# HG0B1CEU.net
KiCad netlist of a schematic drawn in EAGLE
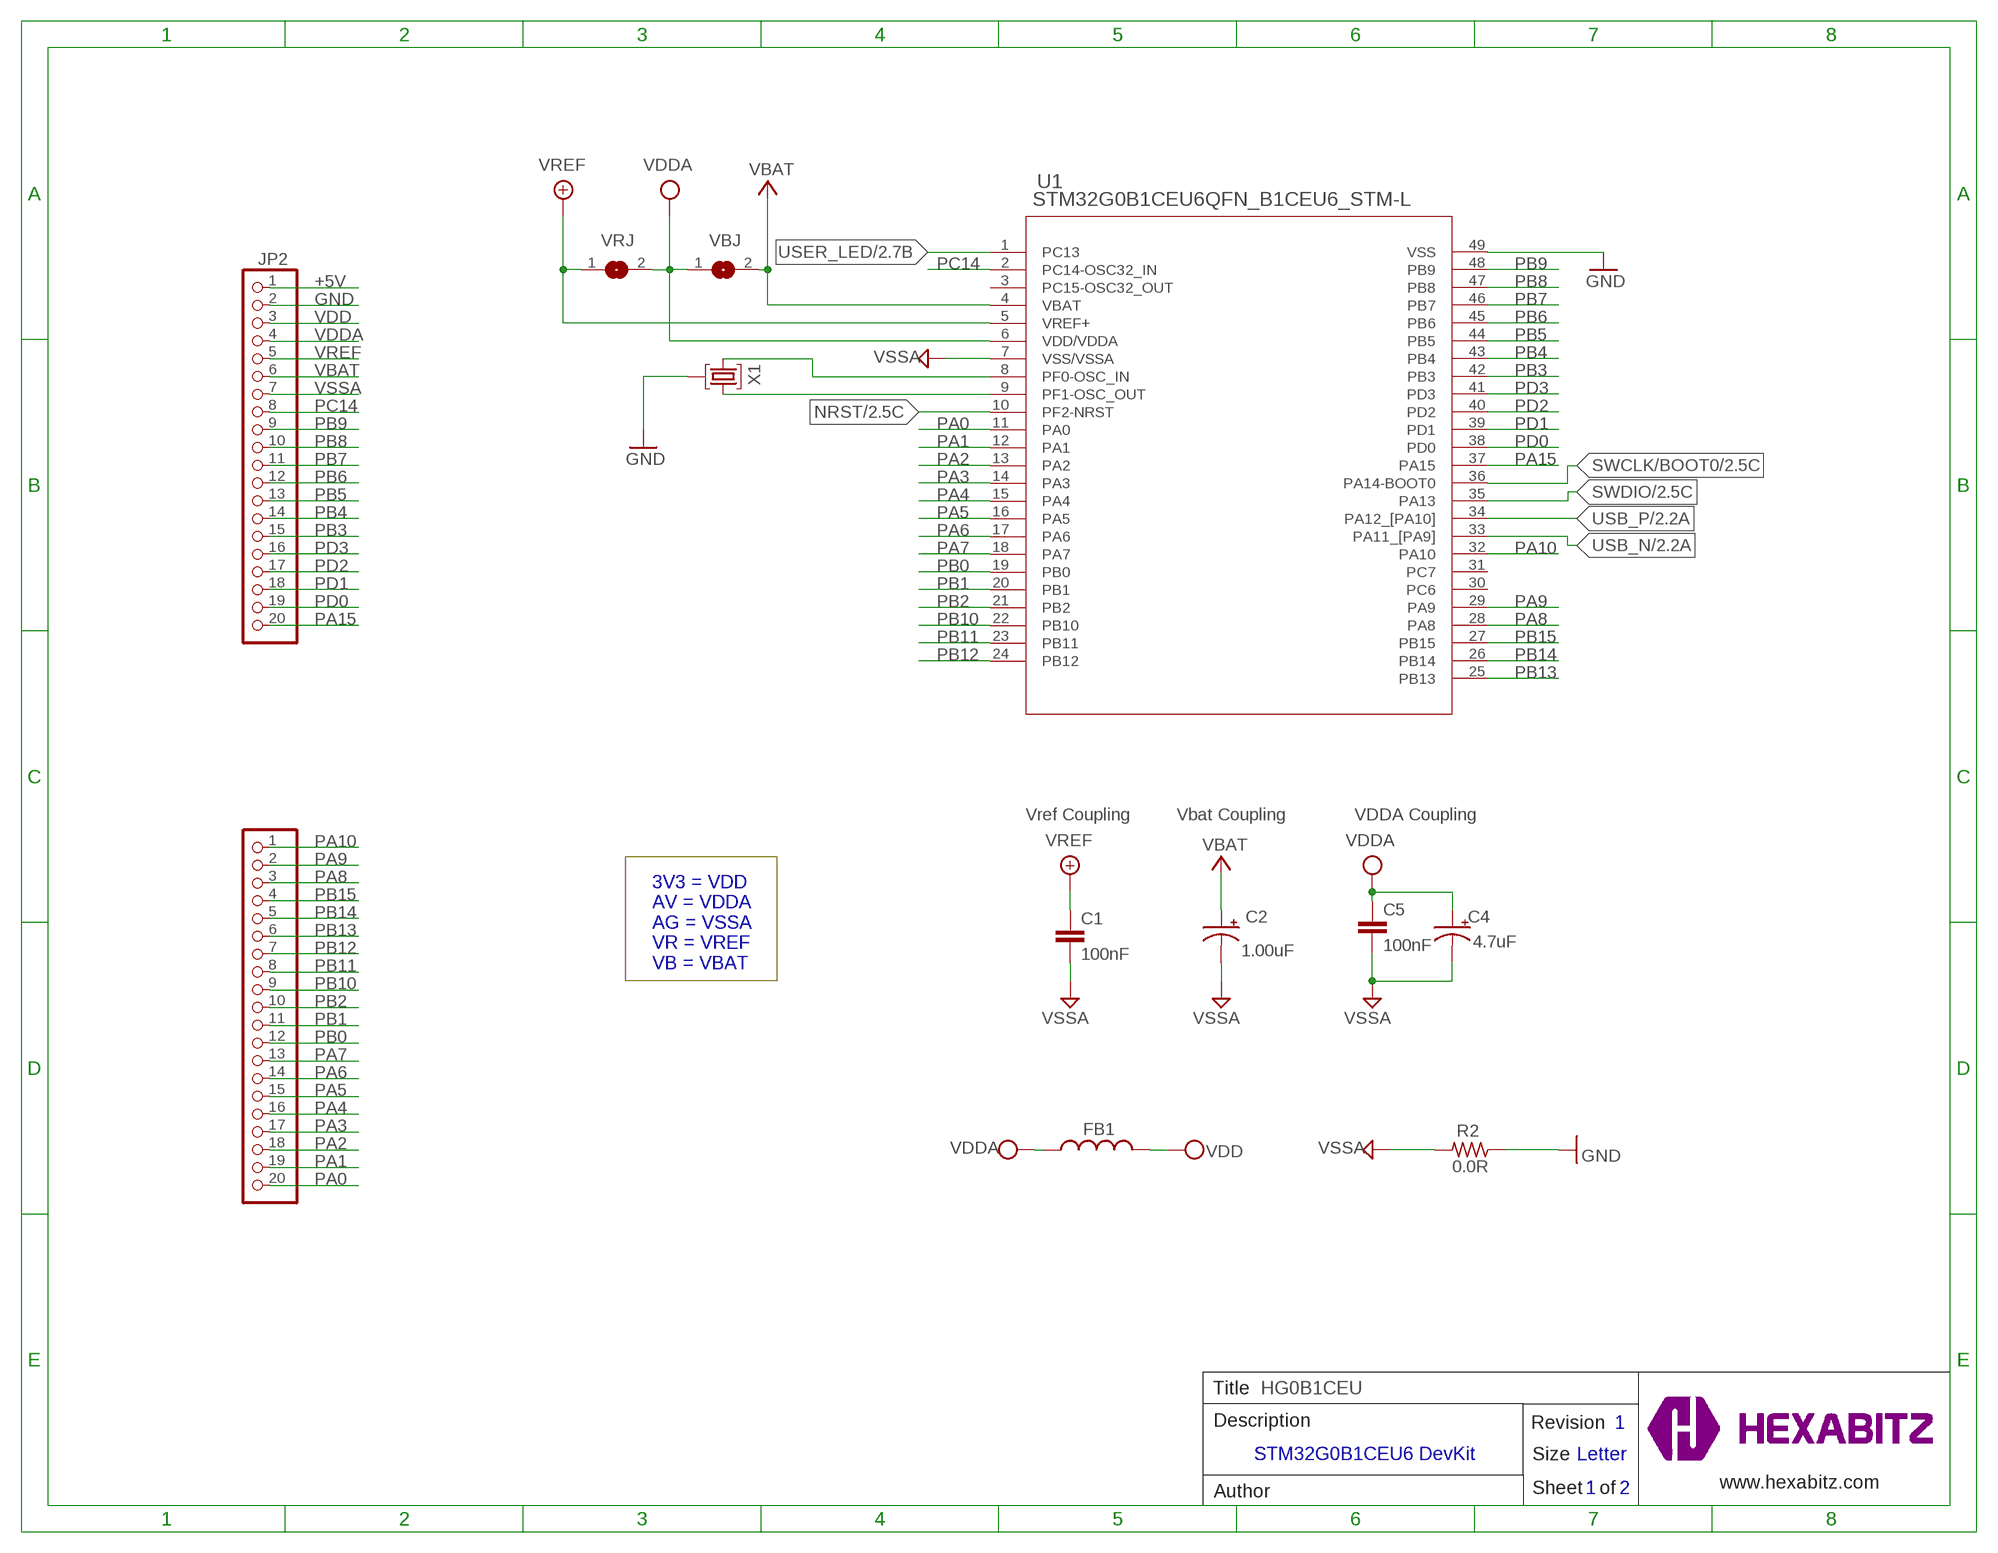
[diagram p0: schematic, sheet 1]
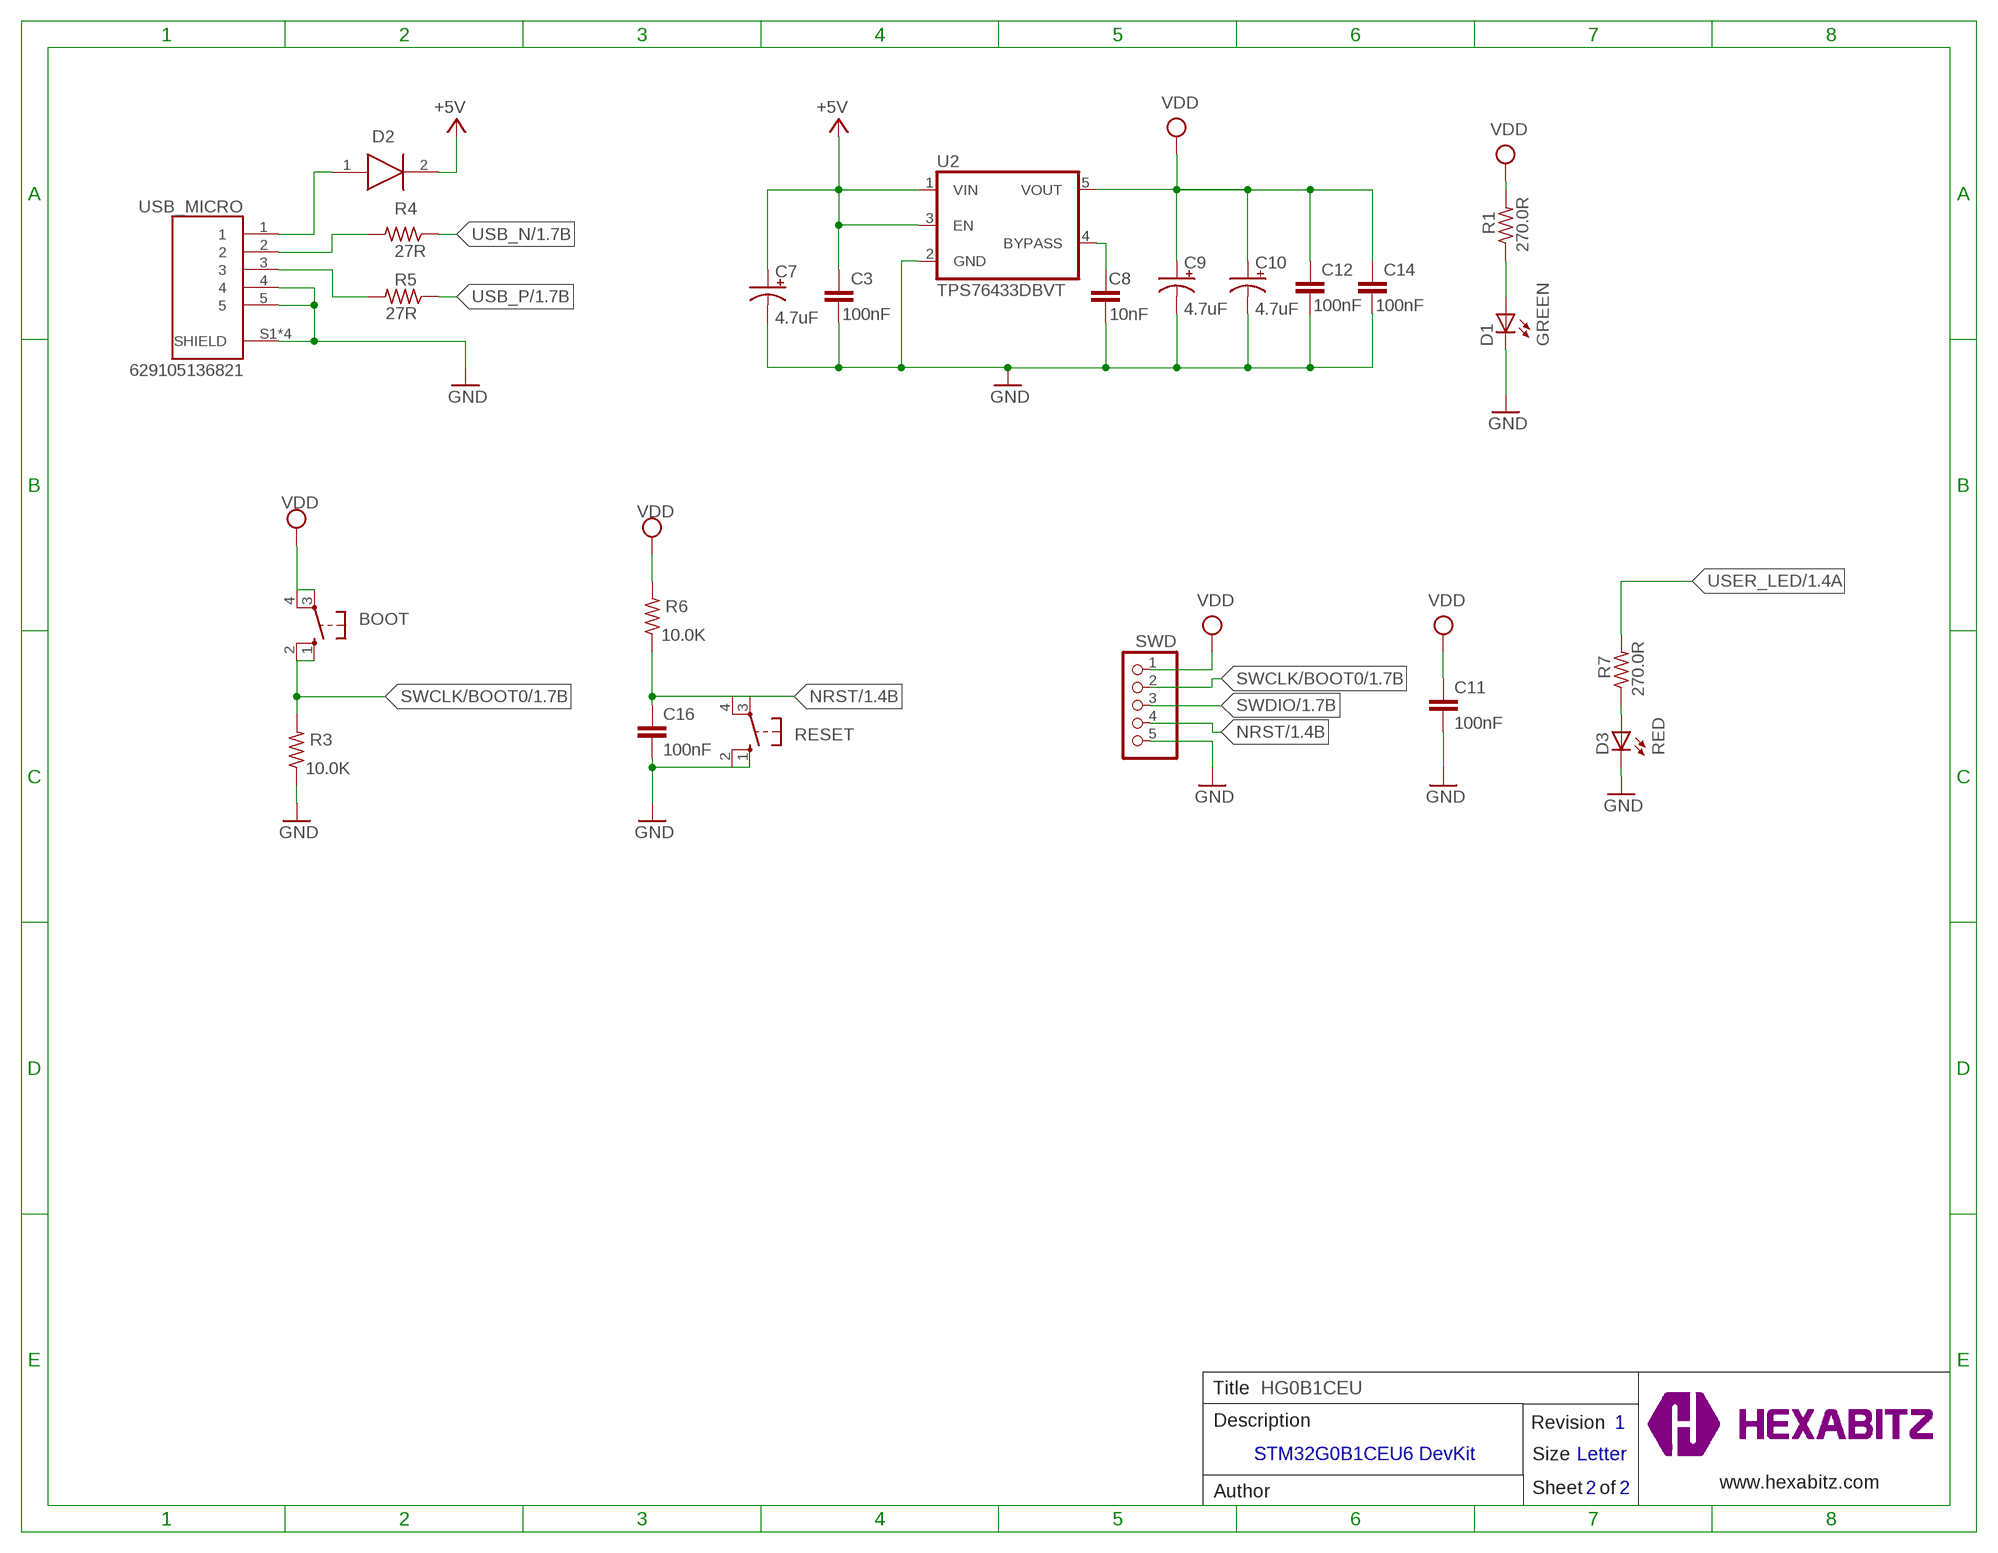
[diagram p1: schematic, sheet 2]

(export (version "E")
  (design (tool "Eeschema 10.0.6"))
  (components
    (comp (ref "BOOT")
      (value "10-XX")
      (footprint "eagle-import:B3F-10XX")
      (fields (field (name "MPN") "B3F-1000"))
      (libsource (lib "eagle-import") (part "10-XX"))
    )
    (comp (ref "C3")
      (value "100nF")
      (footprint "eagle-import:C-0603")
      (fields
        (field (name "CAPACITANCE") "100nF")
        (field (name "MFN") "KEMET")
        (field (name "MPN") "C0603C104K8RACTU")
        (field (name "OCTOPART_URL") "https://octopart.com/c0603c104k8ractu-kemet-145075?r=sp&s=9bS9ASSwSEqMCE9KBEQZ0g")
        (field (name "TOLERANCE") "10%")
        (field (name "VOLTAGE_RATING") "10")
      )
      (libsource (lib "eagle-import") (part "C-0603"))
    )
    (comp (ref "C7")
      (value "4.7uF")
      (footprint "eagle-import:C-0805-POL")
      (fields
        (field (name "CAPACITANCE") "4.7uF")
        (field (name "MFN") "Murata")
        (field (name "MPN") "GRM21BC81E475KA12L")
        (field (name "OCTOPART_URL") "https://octopart.com/grm21bc81e475ka12l-murata-10331911?r=sp&s=RY3qZSD8T6mG6TC9CHI5qQ")
        (field (name "TOLERANCE") "10%")
        (field (name "VOLTAGE_RATING") "25V")
      )
      (libsource (lib "eagle-import") (part "C-0805-POL"))
    )
    (comp (ref "C8")
      (value "10nF")
      (footprint "eagle-import:C-0603")
      (fields
        (field (name "CAPACITANCE") "100nF")
        (field (name "MFN") "KEMET")
        (field (name "MPN") "C0603C104K8RACTU")
        (field (name "OCTOPART_URL") "https://octopart.com/c0603c104k8ractu-kemet-145075?r=sp&s=9bS9ASSwSEqMCE9KBEQZ0g")
        (field (name "TOLERANCE") "10%")
        (field (name "VOLTAGE_RATING") "10")
      )
      (libsource (lib "eagle-import") (part "C-0603"))
    )
    (comp (ref "C9")
      (value "4.7uF")
      (footprint "eagle-import:C-0805-POL")
      (fields
        (field (name "CAPACITANCE") "4.7uF")
        (field (name "MFN") "Murata")
        (field (name "MPN") "GRM21BC81E475KA12L")
        (field (name "OCTOPART_URL") "https://octopart.com/grm21bc81e475ka12l-murata-10331911?r=sp&s=RY3qZSD8T6mG6TC9CHI5qQ")
        (field (name "TOLERANCE") "10%")
        (field (name "VOLTAGE_RATING") "25V")
      )
      (libsource (lib "eagle-import") (part "C-0805-POL"))
    )
    (comp (ref "C10")
      (value "4.7uF")
      (footprint "eagle-import:C-0805-POL")
      (fields
        (field (name "CAPACITANCE") "4.7uF")
        (field (name "MFN") "Murata")
        (field (name "MPN") "GRM21BC81E475KA12L")
        (field (name "OCTOPART_URL") "https://octopart.com/grm21bc81e475ka12l-murata-10331911?r=sp&s=RY3qZSD8T6mG6TC9CHI5qQ")
        (field (name "TOLERANCE") "10%")
        (field (name "VOLTAGE_RATING") "25V")
      )
      (libsource (lib "eagle-import") (part "C-0805-POL"))
    )
    (comp (ref "C11")
      (value "100nF")
      (footprint "eagle-import:C-0603")
      (fields
        (field (name "CAPACITANCE") "100nF")
        (field (name "MFN") "KEMET")
        (field (name "MPN") "C0603C104K8RACTU")
        (field (name "OCTOPART_URL") "https://octopart.com/c0603c104k8ractu-kemet-145075?r=sp&s=9bS9ASSwSEqMCE9KBEQZ0g")
        (field (name "TOLERANCE") "10%")
        (field (name "VOLTAGE_RATING") "10V")
      )
      (libsource (lib "eagle-import") (part "C-0603"))
    )
    (comp (ref "C12")
      (value "100nF")
      (footprint "eagle-import:C-0603")
      (fields
        (field (name "CAPACITANCE") "100nF")
        (field (name "MFN") "KEMET")
        (field (name "MPN") "C0603C104K8RACTU")
        (field (name "OCTOPART_URL") "https://octopart.com/c0603c104k8ractu-kemet-145075?r=sp&s=9bS9ASSwSEqMCE9KBEQZ0g")
        (field (name "TOLERANCE") "10%")
        (field (name "VOLTAGE_RATING") "10")
      )
      (libsource (lib "eagle-import") (part "C-0603"))
    )
    (comp (ref "C14")
      (value "100nF")
      (footprint "eagle-import:C-0603")
      (fields
        (field (name "CAPACITANCE") "100nF")
        (field (name "MFN") "KEMET")
        (field (name "MPN") "C0603C104K8RACTU")
        (field (name "OCTOPART_URL") "https://octopart.com/c0603c104k8ractu-kemet-145075?r=sp&s=9bS9ASSwSEqMCE9KBEQZ0g")
        (field (name "TOLERANCE") "10%")
        (field (name "VOLTAGE_RATING") "10")
      )
      (libsource (lib "eagle-import") (part "C-0603"))
    )
    (comp (ref "C16")
      (value "100nF")
      (footprint "eagle-import:C-0603")
      (fields
        (field (name "CAPACITANCE") "100nF")
        (field (name "MFN") "KEMET")
        (field (name "MPN") "C0603C104K8RACTU")
        (field (name "OCTOPART_URL") "https://octopart.com/c0603c104k8ractu-kemet-145075?r=sp&s=9bS9ASSwSEqMCE9KBEQZ0g")
        (field (name "TOLERANCE") "10%")
        (field (name "VOLTAGE_RATING") "10V")
      )
      (libsource (lib "eagle-import") (part "C-0603"))
    )
    (comp (ref "D1")
      (value "GREEN")
      (footprint "eagle-import:VLMS1300-GS08")
      (fields
        (field (name "MPN") "VLMS1300-GS08")
        (field (name "MFN") "Vishay")
        (field (name "MPN_1") "VLMS1300-GS08")
        (field (name "OCTOPART_URL") "https://octopart.com/vlms1300-gs08-vishay-21709201?r=sp&s=_gcP4_q8T1SC6PJQPTQ9yA")
      )
      (libsource (lib "eagle-import") (part "VLMS1300-GS08"))
    )
    (comp (ref "D2")
      (value "FSM17PL-TP")
      (footprint "eagle-import:FSM17PL-TP")
      (libsource (lib "eagle-import") (part "FSM17PL-TP"))
    )
    (comp (ref "D3")
      (value "RED")
      (footprint "eagle-import:VLMS1300-GS08")
      (fields
        (field (name "MPN") "VLMS1300-GS08")
        (field (name "MFN") "Vishay")
        (field (name "MPN_1") "VLMS1300-GS08")
        (field (name "OCTOPART_URL") "https://octopart.com/vlms1300-gs08-vishay-21709201?r=sp&s=_gcP4_q8T1SC6PJQPTQ9yA")
      )
      (libsource (lib "eagle-import") (part "VLMS1300-GS08"))
    )
    (comp (ref "R1")
      (value "270.0R")
      (footprint "eagle-import:R-0603")
      (fields
        (field (name "MFN") "Yageo")
        (field (name "MPN") "RC0603FR-07270RL")
        (field (name "OCTOPART_URL") "https://octopart.com/search?q=RC0603FR-07270RL&start=0")
        (field (name "RESISTANCE") "270.0 Ohm")
        (field (name "TOLERANCE") "1%")
      )
      (libsource (lib "eagle-import") (part "R-0603"))
    )
    (comp (ref "R3")
      (value "10.0K")
      (footprint "eagle-import:R-0603")
      (fields
        (field (name "MFN") "Yageo")
        (field (name "MPN") "RC0603JR-0710KL")
        (field (name "OCTOPART_URL") "https://octopart.com/search?q=RC0603JR-0710KL&start=0")
        (field (name "RESISTANCE") "10.0K Ohm")
        (field (name "TOLERANCE") "5%")
      )
      (libsource (lib "eagle-import") (part "R-0603"))
    )
    (comp (ref "R4")
      (value "27R")
      (footprint "eagle-import:R-0603")
      (fields
        (field (name "MFN") "Yageo")
        (field (name "MPN") "RC0603JR-0710KL")
        (field (name "OCTOPART_URL") "https://octopart.com/search?q=RC0603JR-0710KL&start=0")
        (field (name "RESISTANCE") "10.0K Ohm")
        (field (name "TOLERANCE") "5%")
      )
      (libsource (lib "eagle-import") (part "R-0603"))
    )
    (comp (ref "R5")
      (value "27R")
      (footprint "eagle-import:R-0603")
      (fields
        (field (name "MFN") "Yageo")
        (field (name "MPN") "RC0603JR-0710KL")
        (field (name "OCTOPART_URL") "https://octopart.com/search?q=RC0603JR-0710KL&start=0")
        (field (name "RESISTANCE") "10.0K Ohm")
        (field (name "TOLERANCE") "5%")
      )
      (libsource (lib "eagle-import") (part "R-0603"))
    )
    (comp (ref "R6")
      (value "10.0K")
      (footprint "eagle-import:R-0603")
      (fields
        (field (name "MFN") "Yageo")
        (field (name "MPN") "RC0603JR-0710KL")
        (field (name "OCTOPART_URL") "https://octopart.com/search?q=RC0603JR-0710KL&start=0")
        (field (name "RESISTANCE") "10.0K Ohm")
        (field (name "TOLERANCE") "5%")
      )
      (libsource (lib "eagle-import") (part "R-0603"))
    )
    (comp (ref "R7")
      (value "270.0R")
      (footprint "eagle-import:R-0603")
      (fields
        (field (name "MFN") "Yageo")
        (field (name "MPN") "RC0603FR-07270RL")
        (field (name "OCTOPART_URL") "https://octopart.com/search?q=RC0603FR-07270RL&start=0")
        (field (name "RESISTANCE") "270.0 Ohm")
        (field (name "TOLERANCE") "1%")
      )
      (libsource (lib "eagle-import") (part "R-0603"))
    )
    (comp (ref "RESET")
      (value "10-XX")
      (footprint "eagle-import:B3F-10XX")
      (fields (field (name "MPN") "B3F-1000"))
      (libsource (lib "eagle-import") (part "10-XX"))
    )
    (comp (ref "SWD")
      (value "PINHD-1X5/90")
      (footprint "eagle-import:1X05_90")
      (libsource (lib "eagle-import") (part "PINHD-1X5/90"))
    )
    (comp (ref "U2")
      (value "TPS76433DBVT")
      (footprint "eagle-import:SOT25")
      (libsource (lib "eagle-import") (part "TPS764DBVT33"))
    )
    (comp (ref "USB_MICRO")
      (value "629105136821")
      (footprint "eagle-import:WE_629105136821")
      (fields (field (name "MF") "Würth Elektronik"))
      (libsource (lib "eagle-import") (part "629105136821"))
    )
    (comp (ref "C1")
      (value "100nF")
      (footprint "eagle-import:C-0603")
      (fields
        (field (name "CAPACITANCE") "100nF")
        (field (name "MFN") "KEMET")
        (field (name "MPN") "C0603C104K8RACTU")
        (field (name "OCTOPART_URL") "https://octopart.com/c0603c104k8ractu-kemet-145075?r=sp&s=9bS9ASSwSEqMCE9KBEQZ0g")
        (field (name "TOLERANCE") "10%")
        (field (name "VOLTAGE_RATING") "10V")
      )
      (libsource (lib "eagle-import") (part "C-0603"))
    )
    (comp (ref "C2")
      (value "1.00uF")
      (footprint "eagle-import:C-0805-POL")
      (fields
        (field (name "CAPACITANCE") "1.00uF")
        (field (name "MFN") "Yageo")
        (field (name "MPN") "CC0805KKX7R7BB105")
        (field (name "OCTOPART_URL") "https://octopart.com/cc0805kkx7r7bb105-yageo-8376555?r=sp&s=YKl1wwtkROau_X5nniH2ig")
        (field (name "TOLERANCE") "10%")
        (field (name "VOLTAGE_RATING") "16V")
      )
      (libsource (lib "eagle-import") (part "C-0805-POL"))
    )
    (comp (ref "C4")
      (value "4.7uF")
      (footprint "eagle-import:C-0805-POL")
      (fields
        (field (name "CAPACITANCE") "4.7uF")
        (field (name "MFN") "Murata")
        (field (name "MPN") "GRM21BC81E475KA12L")
        (field (name "OCTOPART_URL") "https://octopart.com/grm21bc81e475ka12l-murata-10331911?r=sp&s=RY3qZSD8T6mG6TC9CHI5qQ")
        (field (name "TOLERANCE") "10%")
        (field (name "VOLTAGE_RATING") "25V")
      )
      (libsource (lib "eagle-import") (part "C-0805-POL"))
    )
    (comp (ref "C5")
      (value "100nF")
      (footprint "eagle-import:C-0603")
      (fields
        (field (name "CAPACITANCE") "100nF")
        (field (name "MFN") "KEMET")
        (field (name "MPN") "C0603C104K8RACTU")
        (field (name "OCTOPART_URL") "https://octopart.com/c0603c104k8ractu-kemet-145075?r=sp&s=9bS9ASSwSEqMCE9KBEQZ0g")
        (field (name "TOLERANCE") "10%")
        (field (name "VOLTAGE_RATING") "10")
      )
      (libsource (lib "eagle-import") (part "C-0603"))
    )
    (comp (ref "FB1")
      (value "FB-TDK_MMZ1608Y300B")
      (footprint "eagle-import:FB-TDK_MMZ1608Y300B")
      (fields
        (field (name "MFN") "TDK ")
        (field (name "MPN") "MMZ1608Y300B")
        (field (name "OCTOPART_URL") "https://octopart.com/mmz1608y300b-tdk-368280?r=sp&s=cd9_2ZEqQ9q9UNBuQgHAiA")
      )
      (libsource (lib "eagle-import") (part "FB-TDK_MMZ1608Y300B"))
    )
    (comp (ref "JP1")
      (value "PINHD-1X20")
      (footprint "eagle-import:1X20")
      (libsource (lib "eagle-import") (part "PINHD-1X20"))
    )
    (comp (ref "JP2")
      (value "PINHD-1X20")
      (footprint "eagle-import:1X20")
      (libsource (lib "eagle-import") (part "PINHD-1X20"))
    )
    (comp (ref "R2")
      (value "0.0R")
      (footprint "eagle-import:R-0603")
      (fields
        (field (name "MFN") "Yageo")
        (field (name "MPN") "RC0603JR-070RL")
        (field (name "OCTOPART_URL") "https://octopart.com/rc0603jr-070rl-yageo-1241539?r=sp&s=X2NteqRjRNWrnx42Y0aliA")
        (field (name "RESISTANCE") "0.0 Ohm")
      )
      (libsource (lib "eagle-import") (part "R-0603"))
    )
    (comp (ref "U1")
      (value "STM32G0B1CEU6QFN_B1CEU6_STM-L")
      (footprint "eagle-import:QFN_B1CEU6_STM-L")
      (fields
        (field (name "MANUFACTURER_PART_NUMBER") "STM32G0B1CEU6")
        (field (name "COPYRIGHT") "Copyright (C) 2021 Ultra Librarian. All rights reserved.")
      )
      (libsource (lib "eagle-import") (part "STM32G0B1CEU6QFN_B1CEU6_STM-L"))
    )
    (comp (ref "VBJ") (value "SJ") (footprint "eagle-import:SJ") (libsource (lib "eagle-import") (part "SJ")))
    (comp (ref "VRJ") (value "SJ") (footprint "eagle-import:SJ") (libsource (lib "eagle-import") (part "SJ")))
    (comp (ref "X1")
      (value "XTALL_CSTCE8M00G52")
      (footprint "eagle-import:XTALL_CSTCE8M00G52")
      (fields (field (name "MPN") "CSTCE8M00G52Z-R0"))
      (libsource (lib "eagle-import") (part "XTALL_CSTCE8M00G52"))
    )
  )
  (nets
    (net (code "1") (name "+5V") (class "Default")
      (node (ref "C3") (pin "1") (pinfunction "1_1") (pintype "passive"))
      (node (ref "C7") (pin "1") (pinfunction "+_1") (pintype "passive"))
      (node (ref "D2") (pin "2") (pinfunction "K_2") (pintype "bidirectional"))
      (node (ref "JP2") (pin "1") (pinfunction "1_1") (pintype "passive"))
      (node (ref "U2") (pin "1") (pinfunction "VIN_1") (pintype "input"))
      (node (ref "U2") (pin "3") (pinfunction "EN_3") (pintype "input"))
    )
    (net (code "2") (name "GND") (class "Default")
      (node (ref "C10") (pin "2") (pinfunction "-_2") (pintype "passive"))
      (node (ref "C11") (pin "2") (pinfunction "2_2") (pintype "passive"))
      (node (ref "C12") (pin "2") (pinfunction "2_2") (pintype "passive"))
      (node (ref "C14") (pin "2") (pinfunction "2_2") (pintype "passive"))
      (node (ref "C16") (pin "2") (pinfunction "2_2") (pintype "passive"))
      (node (ref "C3") (pin "2") (pinfunction "2_2") (pintype "passive"))
      (node (ref "C7") (pin "2") (pinfunction "-_2") (pintype "passive"))
      (node (ref "C8") (pin "2") (pinfunction "2_2") (pintype "passive"))
      (node (ref "C9") (pin "2") (pinfunction "-_2") (pintype "passive"))
      (node (ref "D1") (pin "C") (pinfunction "C_C") (pintype "passive"))
      (node (ref "D3") (pin "C") (pinfunction "C_C") (pintype "passive"))
      (node (ref "JP2") (pin "2") (pinfunction "2_2") (pintype "passive"))
      (node (ref "R2") (pin "1") (pinfunction "1_1") (pintype "passive"))
      (node (ref "R3") (pin "1") (pinfunction "1_1") (pintype "passive"))
      (node (ref "RESET") (pin "1") (pinfunction "S_1") (pintype "passive"))
      (node (ref "RESET") (pin "2") (pinfunction "S1_2") (pintype "passive"))
      (node (ref "SWD") (pin "5") (pinfunction "5_5") (pintype "passive"))
      (node (ref "U1") (pin "49") (pinfunction "VSS_49") (pintype "passive"))
      (node (ref "U2") (pin "2") (pinfunction "GND_2") (pintype "passive"))
      (node (ref "USB_MICRO") (pin "4") (pinfunction "4_4") (pintype "passive"))
      (node (ref "USB_MICRO") (pin "5") (pinfunction "5_5") (pintype "passive"))
      (node (ref "USB_MICRO") (pin "S1") (pinfunction "SHIELD_S1") (pintype "passive"))
      (node (ref "USB_MICRO") (pin "S2") (pinfunction "SHIELD_S2") (pintype "passive"))
      (node (ref "USB_MICRO") (pin "S3") (pinfunction "SHIELD_S3") (pintype "passive"))
      (node (ref "USB_MICRO") (pin "S4") (pinfunction "SHIELD_S4") (pintype "passive"))
      (node (ref "X1") (pin "P$2") (pinfunction "2_P$2") (pintype "passive"))
    )
    (net (code "3") (name "NRST") (class "Default")
      (node (ref "C16") (pin "1") (pinfunction "1_1") (pintype "passive"))
      (node (ref "R6") (pin "1") (pinfunction "1_1") (pintype "passive"))
      (node (ref "RESET") (pin "3") (pinfunction "P_3") (pintype "passive"))
      (node (ref "RESET") (pin "4") (pinfunction "P1_4") (pintype "passive"))
      (node (ref "SWD") (pin "4") (pinfunction "4_4") (pintype "passive"))
      (node (ref "U1") (pin "10") (pinfunction "PF2-NRST_10") (pintype "bidirectional"))
    )
    (net (code "4") (name "Net-(D1-PadA)") (class "Default")
      (node (ref "D1") (pin "A") (pinfunction "A_A") (pintype "passive"))
      (node (ref "R1") (pin "1") (pinfunction "1_1") (pintype "passive"))
    )
    (net (code "5") (name "Net-(D2-A)") (class "Default")
      (node (ref "D2") (pin "1") (pinfunction "A_1") (pintype "bidirectional"))
      (node (ref "USB_MICRO") (pin "1") (pinfunction "1_1") (pintype "passive"))
    )
    (net (code "6") (name "Net-(D3-PadA)") (class "Default")
      (node (ref "D3") (pin "A") (pinfunction "A_A") (pintype "passive"))
      (node (ref "R7") (pin "1") (pinfunction "1_1") (pintype "passive"))
    )
    (net (code "7") (name "Net-(R4-Pad2)") (class "Default")
      (node (ref "R4") (pin "2") (pinfunction "2_2") (pintype "passive"))
      (node (ref "USB_MICRO") (pin "2") (pinfunction "2_2") (pintype "passive"))
    )
    (net (code "8") (name "Net-(R5-Pad2)") (class "Default")
      (node (ref "R5") (pin "2") (pinfunction "2_2") (pintype "passive"))
      (node (ref "USB_MICRO") (pin "3") (pinfunction "3_3") (pintype "passive"))
    )
    (net (code "9") (name "Net-(U1-PF0-OSC_IN)") (class "Default")
      (node (ref "U1") (pin "8") (pinfunction "PF0-OSC_IN_8") (pintype "bidirectional"))
      (node (ref "X1") (pin "P$1") (pinfunction "1_P$1") (pintype "passive"))
    )
    (net (code "10") (name "Net-(U1-PF1-OSC_OUT)") (class "Default")
      (node (ref "U1") (pin "9") (pinfunction "PF1-OSC_OUT_9") (pintype "output"))
      (node (ref "X1") (pin "P$3") (pinfunction "3_P$3") (pintype "passive"))
    )
    (net (code "11") (name "Net-(U2-BYPASS)") (class "Default")
      (node (ref "C8") (pin "1") (pinfunction "1_1") (pintype "passive"))
      (node (ref "U2") (pin "4") (pinfunction "BYPASS_4") (pintype "input"))
    )
    (net (code "12") (name "PA0") (class "Default")
      (node (ref "JP1") (pin "20") (pinfunction "20_20") (pintype "passive"))
      (node (ref "U1") (pin "11") (pinfunction "PA0_11") (pintype "bidirectional"))
    )
    (net (code "13") (name "PA1") (class "Default")
      (node (ref "JP1") (pin "19") (pinfunction "19_19") (pintype "passive"))
      (node (ref "U1") (pin "12") (pinfunction "PA1_12") (pintype "bidirectional"))
    )
    (net (code "14") (name "PA2") (class "Default")
      (node (ref "JP1") (pin "18") (pinfunction "18_18") (pintype "passive"))
      (node (ref "U1") (pin "13") (pinfunction "PA2_13") (pintype "bidirectional"))
    )
    (net (code "15") (name "PA3") (class "Default")
      (node (ref "JP1") (pin "17") (pinfunction "17_17") (pintype "passive"))
      (node (ref "U1") (pin "14") (pinfunction "PA3_14") (pintype "bidirectional"))
    )
    (net (code "16") (name "PA4") (class "Default")
      (node (ref "JP1") (pin "16") (pinfunction "16_16") (pintype "passive"))
      (node (ref "U1") (pin "15") (pinfunction "PA4_15") (pintype "bidirectional"))
    )
    (net (code "17") (name "PA5") (class "Default")
      (node (ref "JP1") (pin "15") (pinfunction "15_15") (pintype "passive"))
      (node (ref "U1") (pin "16") (pinfunction "PA5_16") (pintype "bidirectional"))
    )
    (net (code "18") (name "PA6") (class "Default")
      (node (ref "JP1") (pin "14") (pinfunction "14_14") (pintype "passive"))
      (node (ref "U1") (pin "17") (pinfunction "PA6_17") (pintype "bidirectional"))
    )
    (net (code "19") (name "PA7") (class "Default")
      (node (ref "JP1") (pin "13") (pinfunction "13_13") (pintype "passive"))
      (node (ref "U1") (pin "18") (pinfunction "PA7_18") (pintype "bidirectional"))
    )
    (net (code "20") (name "PA8") (class "Default")
      (node (ref "JP1") (pin "3") (pinfunction "3_3") (pintype "passive"))
      (node (ref "U1") (pin "28") (pinfunction "PA8_28") (pintype "bidirectional"))
    )
    (net (code "21") (name "PA9") (class "Default")
      (node (ref "JP1") (pin "2") (pinfunction "2_2") (pintype "passive"))
      (node (ref "U1") (pin "29") (pinfunction "PA9_29") (pintype "bidirectional"))
    )
    (net (code "22") (name "PA10") (class "Default")
      (node (ref "JP1") (pin "1") (pinfunction "1_1") (pintype "passive"))
      (node (ref "U1") (pin "32") (pinfunction "PA10_32") (pintype "bidirectional"))
    )
    (net (code "23") (name "PA15") (class "Default")
      (node (ref "JP2") (pin "20") (pinfunction "20_20") (pintype "passive"))
      (node (ref "U1") (pin "37") (pinfunction "PA15_37") (pintype "bidirectional"))
    )
    (net (code "24") (name "PB0") (class "Default")
      (node (ref "JP1") (pin "12") (pinfunction "12_12") (pintype "passive"))
      (node (ref "U1") (pin "19") (pinfunction "PB0_19") (pintype "bidirectional"))
    )
    (net (code "25") (name "PB1") (class "Default")
      (node (ref "JP1") (pin "11") (pinfunction "11_11") (pintype "passive"))
      (node (ref "U1") (pin "20") (pinfunction "PB1_20") (pintype "bidirectional"))
    )
    (net (code "26") (name "PB2") (class "Default")
      (node (ref "JP1") (pin "10") (pinfunction "10_10") (pintype "passive"))
      (node (ref "U1") (pin "21") (pinfunction "PB2_21") (pintype "bidirectional"))
    )
    (net (code "27") (name "PB3") (class "Default")
      (node (ref "JP2") (pin "15") (pinfunction "15_15") (pintype "passive"))
      (node (ref "U1") (pin "42") (pinfunction "PB3_42") (pintype "bidirectional"))
    )
    (net (code "28") (name "PB4") (class "Default")
      (node (ref "JP2") (pin "14") (pinfunction "14_14") (pintype "passive"))
      (node (ref "U1") (pin "43") (pinfunction "PB4_43") (pintype "bidirectional"))
    )
    (net (code "29") (name "PB5") (class "Default")
      (node (ref "JP2") (pin "13") (pinfunction "13_13") (pintype "passive"))
      (node (ref "U1") (pin "44") (pinfunction "PB5_44") (pintype "bidirectional"))
    )
    (net (code "30") (name "PB6") (class "Default")
      (node (ref "JP2") (pin "12") (pinfunction "12_12") (pintype "passive"))
      (node (ref "U1") (pin "45") (pinfunction "PB6_45") (pintype "bidirectional"))
    )
    (net (code "31") (name "PB7") (class "Default")
      (node (ref "JP2") (pin "11") (pinfunction "11_11") (pintype "passive"))
      (node (ref "U1") (pin "46") (pinfunction "PB7_46") (pintype "bidirectional"))
    )
    (net (code "32") (name "PB8") (class "Default")
      (node (ref "JP2") (pin "10") (pinfunction "10_10") (pintype "passive"))
      (node (ref "U1") (pin "47") (pinfunction "PB8_47") (pintype "bidirectional"))
    )
    (net (code "33") (name "PB9") (class "Default")
      (node (ref "JP2") (pin "9") (pinfunction "9_9") (pintype "passive"))
      (node (ref "U1") (pin "48") (pinfunction "PB9_48") (pintype "bidirectional"))
    )
    (net (code "34") (name "PB10") (class "Default")
      (node (ref "JP1") (pin "9") (pinfunction "9_9") (pintype "passive"))
      (node (ref "U1") (pin "22") (pinfunction "PB10_22") (pintype "bidirectional"))
    )
    (net (code "35") (name "PB11") (class "Default")
      (node (ref "JP1") (pin "8") (pinfunction "8_8") (pintype "passive"))
      (node (ref "U1") (pin "23") (pinfunction "PB11_23") (pintype "bidirectional"))
    )
    (net (code "36") (name "PB12") (class "Default")
      (node (ref "JP1") (pin "7") (pinfunction "7_7") (pintype "passive"))
      (node (ref "U1") (pin "24") (pinfunction "PB12_24") (pintype "bidirectional"))
    )
    (net (code "37") (name "PB13") (class "Default")
      (node (ref "JP1") (pin "6") (pinfunction "6_6") (pintype "passive"))
      (node (ref "U1") (pin "25") (pinfunction "PB13_25") (pintype "bidirectional"))
    )
    (net (code "38") (name "PB14") (class "Default")
      (node (ref "JP1") (pin "5") (pinfunction "5_5") (pintype "passive"))
      (node (ref "U1") (pin "26") (pinfunction "PB14_26") (pintype "bidirectional"))
    )
    (net (code "39") (name "PB15") (class "Default")
      (node (ref "JP1") (pin "4") (pinfunction "4_4") (pintype "passive"))
      (node (ref "U1") (pin "27") (pinfunction "PB15_27") (pintype "bidirectional"))
    )
    (net (code "40") (name "PC14") (class "Default")
      (node (ref "JP2") (pin "8") (pinfunction "8_8") (pintype "passive"))
      (node (ref "U1") (pin "2") (pinfunction "PC14-OSC32_IN_2") (pintype "bidirectional"))
    )
    (net (code "41") (name "PD0") (class "Default")
      (node (ref "JP2") (pin "19") (pinfunction "19_19") (pintype "passive"))
      (node (ref "U1") (pin "38") (pinfunction "PD0_38") (pintype "bidirectional"))
    )
    (net (code "42") (name "PD1") (class "Default")
      (node (ref "JP2") (pin "18") (pinfunction "18_18") (pintype "passive"))
      (node (ref "U1") (pin "39") (pinfunction "PD1_39") (pintype "bidirectional"))
    )
    (net (code "43") (name "PD2") (class "Default")
      (node (ref "JP2") (pin "17") (pinfunction "17_17") (pintype "passive"))
      (node (ref "U1") (pin "40") (pinfunction "PD2_40") (pintype "bidirectional"))
    )
    (net (code "44") (name "PD3") (class "Default")
      (node (ref "JP2") (pin "16") (pinfunction "16_16") (pintype "passive"))
      (node (ref "U1") (pin "41") (pinfunction "PD3_41") (pintype "bidirectional"))
    )
    (net (code "45") (name "SWCLK{slash}BOOT0") (class "Default")
      (node (ref "BOOT") (pin "1") (pinfunction "S_1") (pintype "passive"))
      (node (ref "BOOT") (pin "2") (pinfunction "S1_2") (pintype "passive"))
      (node (ref "R3") (pin "2") (pinfunction "2_2") (pintype "passive"))
      (node (ref "SWD") (pin "2") (pinfunction "2_2") (pintype "passive"))
      (node (ref "U1") (pin "36") (pinfunction "PA14-BOOT0_36") (pintype "bidirectional"))
    )
    (net (code "46") (name "SWDIO") (class "Default")
      (node (ref "SWD") (pin "3") (pinfunction "3_3") (pintype "passive"))
      (node (ref "U1") (pin "35") (pinfunction "PA13_35") (pintype "bidirectional"))
    )
    (net (code "47") (name "USB_N") (class "Default")
      (node (ref "R4") (pin "1") (pinfunction "1_1") (pintype "passive"))
      (node (ref "U1") (pin "33") (pinfunction "PA11_[PA9]_33") (pintype "bidirectional"))
    )
    (net (code "48") (name "USB_P") (class "Default")
      (node (ref "R5") (pin "1") (pinfunction "1_1") (pintype "passive"))
      (node (ref "U1") (pin "34") (pinfunction "PA12_[PA10]_34") (pintype "bidirectional"))
    )
    (net (code "49") (name "USER_LED") (class "Default")
      (node (ref "R7") (pin "2") (pinfunction "2_2") (pintype "passive"))
      (node (ref "U1") (pin "1") (pinfunction "PC13_1") (pintype "bidirectional"))
    )
    (net (code "50") (name "VBAT") (class "Default")
      (node (ref "C2") (pin "1") (pinfunction "+_1") (pintype "passive"))
      (node (ref "JP2") (pin "6") (pinfunction "6_6") (pintype "passive"))
      (node (ref "U1") (pin "4") (pinfunction "VBAT_4") (pintype "passive"))
      (node (ref "VBJ") (pin "2") (pinfunction "2_2") (pintype "passive"))
    )
    (net (code "51") (name "VDD") (class "Default")
      (node (ref "BOOT") (pin "3") (pinfunction "P_3") (pintype "passive"))
      (node (ref "BOOT") (pin "4") (pinfunction "P1_4") (pintype "passive"))
      (node (ref "C10") (pin "1") (pinfunction "+_1") (pintype "passive"))
      (node (ref "C11") (pin "1") (pinfunction "1_1") (pintype "passive"))
      (node (ref "C12") (pin "1") (pinfunction "1_1") (pintype "passive"))
      (node (ref "C14") (pin "1") (pinfunction "1_1") (pintype "passive"))
      (node (ref "C9") (pin "1") (pinfunction "+_1") (pintype "passive"))
      (node (ref "FB1") (pin "2") (pinfunction "2_2") (pintype "passive"))
      (node (ref "JP2") (pin "3") (pinfunction "3_3") (pintype "passive"))
      (node (ref "R1") (pin "2") (pinfunction "2_2") (pintype "passive"))
      (node (ref "R6") (pin "2") (pinfunction "2_2") (pintype "passive"))
      (node (ref "SWD") (pin "1") (pinfunction "1_1") (pintype "passive"))
      (node (ref "U2") (pin "5") (pinfunction "VOUT_5") (pintype "passive"))
    )
    (net (code "52") (name "VDDA") (class "Default")
      (node (ref "C4") (pin "1") (pinfunction "+_1") (pintype "passive"))
      (node (ref "C5") (pin "1") (pinfunction "1_1") (pintype "passive"))
      (node (ref "FB1") (pin "1") (pinfunction "1_1") (pintype "passive"))
      (node (ref "JP2") (pin "4") (pinfunction "4_4") (pintype "passive"))
      (node (ref "U1") (pin "6") (pinfunction "VDD/VDDA_6") (pintype "power_in"))
      (node (ref "VBJ") (pin "1") (pinfunction "1_1") (pintype "passive"))
      (node (ref "VRJ") (pin "2") (pinfunction "2_2") (pintype "passive"))
    )
    (net (code "53") (name "VREF") (class "Default")
      (node (ref "C1") (pin "1") (pinfunction "1_1") (pintype "passive"))
      (node (ref "JP2") (pin "5") (pinfunction "5_5") (pintype "passive"))
      (node (ref "U1") (pin "5") (pinfunction "VREF+_5") (pintype "power_in"))
      (node (ref "VRJ") (pin "1") (pinfunction "1_1") (pintype "passive"))
    )
    (net (code "54") (name "VSSA") (class "Default")
      (node (ref "C1") (pin "2") (pinfunction "2_2") (pintype "passive"))
      (node (ref "C2") (pin "2") (pinfunction "-_2") (pintype "passive"))
      (node (ref "C4") (pin "2") (pinfunction "-_2") (pintype "passive"))
      (node (ref "C5") (pin "2") (pinfunction "2_2") (pintype "passive"))
      (node (ref "JP2") (pin "7") (pinfunction "7_7") (pintype "passive"))
      (node (ref "R2") (pin "2") (pinfunction "2_2") (pintype "passive"))
      (node (ref "U1") (pin "7") (pinfunction "VSS/VSSA_7") (pintype "passive"))
    )
    (net (code "55") (name "unconnected-(U1-PC6-Pad30)") (class "Default")
      (node (ref "U1") (pin "30") (pinfunction "PC6_30") (pintype "bidirectional"))
    )
    (net (code "56") (name "unconnected-(U1-PC7-Pad31)") (class "Default")
      (node (ref "U1") (pin "31") (pinfunction "PC7_31") (pintype "bidirectional"))
    )
    (net (code "57") (name "unconnected-(U1-PC15-OSC32_OUT-Pad3)") (class "Default")
      (node (ref "U1") (pin "3") (pinfunction "PC15-OSC32_OUT_3") (pintype "output"))
    )
  )
)
